# 16V3_EDA.net
KiCad netlist of a schematic drawn in EasyEDA Pro
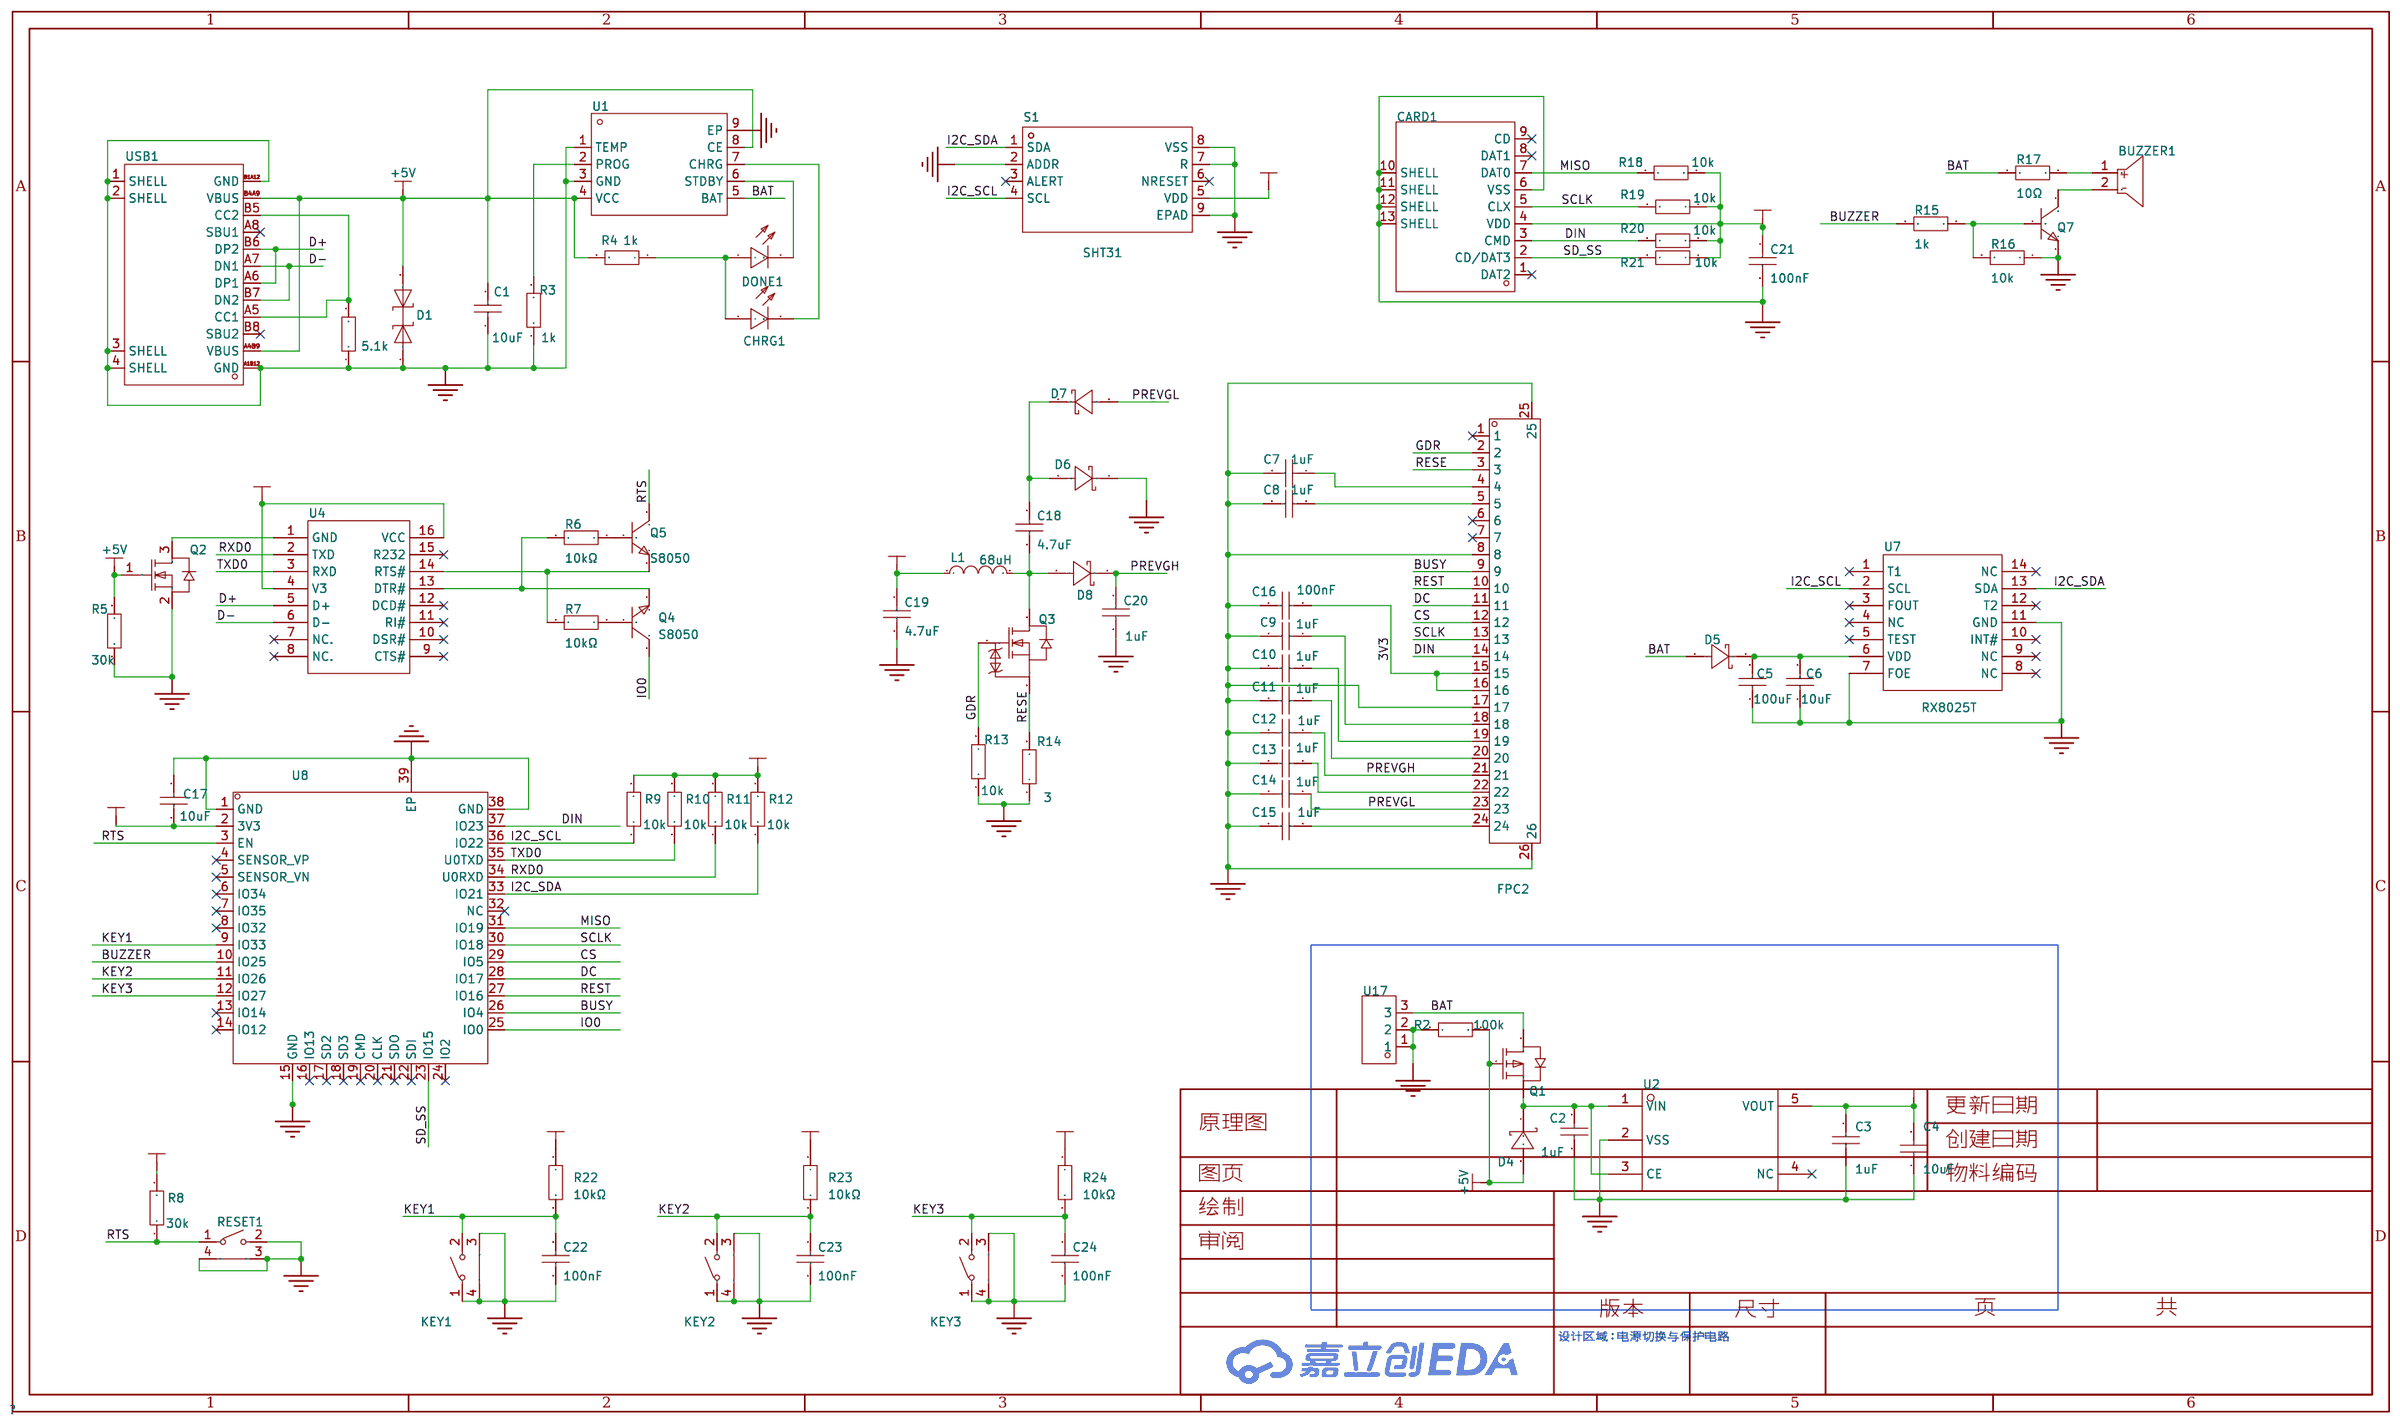
[diagram p0: schematic sheet]

(export (version "E")
  (design (tool "Eeschema 10.0.6"))
  (components
    (comp (ref "BUZZER1")
      (value "FMQ-BUZZER2")
      (footprint "easyedapro:BUZ-TH_BD12.0-P7.60-D0.6-FD")
      (libsource (lib "easyedapro") (part "FMQ-BUZZER2"))
    )
    (comp (ref "C1")
      (value "10uF")
      (footprint "easyedapro:C0805")
      (fields
        (field (name "Manufacturer Part") "CC0805KRX7R9BB104")
        (field (name "Manufacturer") "YAGEO(国巨)")
      )
      (libsource (lib "easyedapro") (part "CC0805KRX7R9BB104"))
    )
    (comp (ref "C2")
      (value "1uF")
      (footprint "easyedapro:C0805")
      (fields
        (field (name "Manufacturer Part") "CC0805KRX7R9BB104")
        (field (name "Manufacturer") "YAGEO(国巨)")
      )
      (libsource (lib "easyedapro") (part "CC0805KRX7R9BB104"))
    )
    (comp (ref "C3")
      (value "1uF")
      (footprint "easyedapro:C0805")
      (fields
        (field (name "Manufacturer Part") "CC0805KRX7R9BB104")
        (field (name "Manufacturer") "YAGEO(国巨)")
      )
      (libsource (lib "easyedapro") (part "CC0805KRX7R9BB104"))
    )
    (comp (ref "C4")
      (value "10uF")
      (footprint "easyedapro:C0805")
      (fields
        (field (name "Manufacturer Part") "CC0805KRX7R9BB104")
        (field (name "Manufacturer") "YAGEO(国巨)")
      )
      (libsource (lib "easyedapro") (part "CC0805KRX7R9BB104"))
    )
    (comp (ref "C5")
      (value "100uF")
      (footprint "easyedapro:C0805")
      (description "容值:100nF;精度:±10%;额定电压:50V;温度系数:X7R;")
      (fields
        (field (name "Manufacturer Part") "CC0805KRX7R9BB104")
        (field (name "Manufacturer") "YAGEO(国巨)")
      )
      (libsource (lib "easyedapro") (part "CC0805KRX7R9BB104"))
    )
    (comp (ref "C6")
      (value "10uF")
      (footprint "easyedapro:C0805")
      (fields
        (field (name "Manufacturer Part") "CC0805KRX7R9BB104")
        (field (name "Manufacturer") "YAGEO(国巨)")
      )
      (libsource (lib "easyedapro") (part "CC0805KRX7R9BB104"))
    )
    (comp (ref "C7")
      (value "1uF")
      (footprint "easyedapro:C0805")
      (fields
        (field (name "Manufacturer Part") "CC0805KRX7R9BB104")
        (field (name "Manufacturer") "YAGEO(国巨)")
      )
      (libsource (lib "easyedapro") (part "CC0805KRX7R9BB104"))
    )
    (comp (ref "C8")
      (value "1uF")
      (footprint "easyedapro:C0805")
      (fields
        (field (name "Manufacturer Part") "CC0805KRX7R9BB104")
        (field (name "Manufacturer") "YAGEO(国巨)")
      )
      (libsource (lib "easyedapro") (part "CC0805KRX7R9BB104"))
    )
    (comp (ref "C9")
      (value "1uF")
      (footprint "easyedapro:C0805")
      (fields
        (field (name "Manufacturer Part") "CC0805KRX7R9BB104")
        (field (name "Manufacturer") "YAGEO(国巨)")
      )
      (libsource (lib "easyedapro") (part "CC0805KRX7R9BB104"))
    )
    (comp (ref "C10")
      (value "1uF")
      (footprint "easyedapro:C0805")
      (fields
        (field (name "Manufacturer Part") "CC0805KRX7R9BB104")
        (field (name "Manufacturer") "YAGEO(国巨)")
      )
      (libsource (lib "easyedapro") (part "CC0805KRX7R9BB104"))
    )
    (comp (ref "C11")
      (value "1uF")
      (footprint "easyedapro:C0805")
      (fields
        (field (name "Manufacturer Part") "CC0805KRX7R9BB104")
        (field (name "Manufacturer") "YAGEO(国巨)")
      )
      (libsource (lib "easyedapro") (part "CC0805KRX7R9BB104"))
    )
    (comp (ref "C12")
      (value "1uF")
      (footprint "easyedapro:C0805")
      (fields
        (field (name "Manufacturer Part") "CC0805KRX7R9BB104")
        (field (name "Manufacturer") "YAGEO(国巨)")
      )
      (libsource (lib "easyedapro") (part "CC0805KRX7R9BB104"))
    )
    (comp (ref "C13")
      (value "1uF")
      (footprint "easyedapro:C0805")
      (fields
        (field (name "Manufacturer Part") "CC0805KRX7R9BB104")
        (field (name "Manufacturer") "YAGEO(国巨)")
      )
      (libsource (lib "easyedapro") (part "CC0805KRX7R9BB104"))
    )
    (comp (ref "C14")
      (value "1uF")
      (footprint "easyedapro:C0805")
      (fields
        (field (name "Manufacturer Part") "CC0805KRX7R9BB104")
        (field (name "Manufacturer") "YAGEO(国巨)")
      )
      (libsource (lib "easyedapro") (part "CC0805KRX7R9BB104"))
    )
    (comp (ref "C15")
      (value "1uF")
      (footprint "easyedapro:C0805")
      (fields
        (field (name "Manufacturer Part") "CC0805KRX7R9BB104")
        (field (name "Manufacturer") "YAGEO(国巨)")
      )
      (libsource (lib "easyedapro") (part "CC0805KRX7R9BB104"))
    )
    (comp (ref "C16")
      (value "100nF")
      (footprint "easyedapro:C0805")
      (description "容值:100nF;精度:±10%;额定电压:50V;温度系数:X7R;")
      (fields
        (field (name "Manufacturer Part") "CC0805KRX7R9BB104")
        (field (name "Manufacturer") "YAGEO(国巨)")
      )
      (libsource (lib "easyedapro") (part "CC0805KRX7R9BB104"))
    )
    (comp (ref "C17")
      (value "10uF")
      (footprint "easyedapro:C0805")
      (fields
        (field (name "Manufacturer Part") "CC0805KRX7R9BB104")
        (field (name "Manufacturer") "YAGEO(国巨)")
      )
      (libsource (lib "easyedapro") (part "CC0805KRX7R9BB104"))
    )
    (comp (ref "C18")
      (value "4.7uF")
      (footprint "easyedapro:C0805")
      (description "容值:100nF;精度:±10%;额定电压:50V;温度系数:X7R;")
      (fields
        (field (name "Manufacturer Part") "CC0805KRX7R9BB104")
        (field (name "Manufacturer") "YAGEO(国巨)")
      )
      (libsource (lib "easyedapro") (part "CC0805KRX7R9BB104"))
    )
    (comp (ref "C19")
      (value "4.7uF")
      (footprint "easyedapro:C0805")
      (fields
        (field (name "Manufacturer Part") "CC0805KRX7R9BB104")
        (field (name "Manufacturer") "YAGEO(国巨)")
      )
      (libsource (lib "easyedapro") (part "CC0805KRX7R9BB104"))
    )
    (comp (ref "C20")
      (value "1uF")
      (footprint "easyedapro:C0805")
      (fields
        (field (name "Manufacturer Part") "CC0805KRX7R9BB104")
        (field (name "Manufacturer") "YAGEO(国巨)")
      )
      (libsource (lib "easyedapro") (part "CC0805KRX7R9BB104"))
    )
    (comp (ref "C21")
      (value "100nF")
      (footprint "easyedapro:C0805")
      (description "容值:100nF;精度:±10%;额定电压:50V;温度系数:X7R;")
      (fields
        (field (name "Manufacturer Part") "CC0805KRX7R9BB104")
        (field (name "Manufacturer") "YAGEO(国巨)")
      )
      (libsource (lib "easyedapro") (part "CC0805KRX7R9BB104"))
    )
    (comp (ref "C22")
      (value "100nF")
      (footprint "easyedapro:C0805")
      (fields
        (field (name "Manufacturer Part") "CC0805KRX7R9BB104")
        (field (name "Manufacturer") "YAGEO(国巨)")
      )
      (libsource (lib "easyedapro") (part "CC0805KRX7R9BB104"))
    )
    (comp (ref "C23")
      (value "100nF")
      (footprint "easyedapro:C0805")
      (fields
        (field (name "Manufacturer Part") "CC0805KRX7R9BB104")
        (field (name "Manufacturer") "YAGEO(国巨)")
      )
      (libsource (lib "easyedapro") (part "CC0805KRX7R9BB104"))
    )
    (comp (ref "C24")
      (value "100nF")
      (footprint "easyedapro:C0805")
      (fields
        (field (name "Manufacturer Part") "CC0805KRX7R9BB104")
        (field (name "Manufacturer") "YAGEO(国巨)")
      )
      (libsource (lib "easyedapro") (part "CC0805KRX7R9BB104"))
    )
    (comp (ref "CARD1")
      (value "~")
      (footprint "easyedapro:TF-SMD_THD2528-11SD-GF")
      (description "卡连接方式:自弹式;卡类型:MicroSD卡(TF卡);连接器类型:卡座;本体最大高度:2mm;工作温度范围:-;")
      (fields (field (name "Manufacturer Part") "THD2528-11SD-GF") (field (name "Manufacturer") "THD(台华达)"))
      (libsource (lib "easyedapro") (part "THD2528-11SD-GF"))
    )
    (comp (ref "CHRG1")
      (value "~")
      (footprint "easyedapro:LED0603-R-RD")
      (fields
        (field (name "Manufacturer Part") "19-217/R6C-AL1M2VY/3T")
        (field (name "Manufacturer") "EVERLIGHT(台湾亿光)")
      )
      (libsource (lib "easyedapro") (part "19-217/R6C-AL1M2VY/3T"))
    )
    (comp (ref "D1")
      (value "~")
      (footprint "easyedapro:SOD-523_L1.2-W0.8-LS1.6-BI")
      (description "极性:双向;反向截止电压(Vrwm):5V@(最大值);击穿电压(最小值):5.6V;峰值脉冲电流(Ipp)@10/1000s:4A;最大钳位电压:12V;")
      (fields (field (name "Manufacturer Part") "ESD5Z5.0VC") (field (name "Manufacturer") "TC(德昌)"))
      (libsource (lib "easyedapro") (part "ESD5Z5.0VC"))
    )
    (comp (ref "D4")
      (value "~")
      (footprint "easyedapro:SMA_L4.3-W2.6-LS5.1-RD")
      (description "直流反向耐压(Vr):40V;平均整流电流(Io):3A;正向压降(Vf):550mV@3A;")
      (fields (field (name "Manufacturer Part") "SS34") (field (name "Manufacturer") "SINO-IC(光宇睿芯)"))
      (libsource (lib "easyedapro") (part "SS34_C355267"))
    )
    (comp (ref "D5")
      (value "~")
      (footprint "easyedapro:SOD-123_L2.7-W1.6-LS3.7-RD-1")
      (description "直流反向耐压(Vr):30V;平均整流电流(Io):500mA;正向压降(Vf):550mV@500mA;")
      (fields (field (name "Manufacturer Part") "MBR0530") (field (name "Manufacturer") "YANGJIE(扬杰)"))
      (libsource (lib "easyedapro") (part "MBR0530_C699108"))
    )
    (comp (ref "D6")
      (value "~")
      (footprint "easyedapro:SOD-123_L2.7-W1.6-LS3.7-RD-1")
      (description "直流反向耐压(Vr):30V;平均整流电流(Io):500mA;正向压降(Vf):550mV@500mA;")
      (fields (field (name "Manufacturer Part") "MBR0530") (field (name "Manufacturer") "YANGJIE(扬杰)"))
      (libsource (lib "easyedapro") (part "MBR0530_C699108"))
    )
    (comp (ref "D7")
      (value "~")
      (footprint "easyedapro:SOD-123_L2.7-W1.6-LS3.7-RD-1")
      (description "直流反向耐压(Vr):30V;平均整流电流(Io):500mA;正向压降(Vf):550mV@500mA;")
      (fields (field (name "Manufacturer Part") "MBR0530") (field (name "Manufacturer") "YANGJIE(扬杰)"))
      (libsource (lib "easyedapro") (part "MBR0530_C699108"))
    )
    (comp (ref "D8")
      (value "~")
      (footprint "easyedapro:SOD-123_L2.7-W1.6-LS3.7-RD-1")
      (description "直流反向耐压(Vr):30V;平均整流电流(Io):500mA;正向压降(Vf):550mV@500mA;")
      (fields (field (name "Manufacturer Part") "MBR0530") (field (name "Manufacturer") "YANGJIE(扬杰)"))
      (libsource (lib "easyedapro") (part "MBR0530_C699108"))
    )
    (comp (ref "DONE1")
      (value "~")
      (footprint "easyedapro:LED0603-R-RD")
      (fields
        (field (name "Manufacturer Part") "19-217/R6C-AL1M2VY/3T")
        (field (name "Manufacturer") "EVERLIGHT(台湾亿光)")
      )
      (libsource (lib "easyedapro") (part "19-217/R6C-AL1M2VY/3T"))
    )
    (comp (ref "FPC2")
      (value "~")
      (footprint "easyedapro:FPC-SMD_24P-L17.5-W5.4-P0.50")
      (description "间距:0.5mm;触点数量:24;锁定特性:抽屉式;安装类型:卧贴;触点类型:上接;")
      (fields (field (name "Manufacturer Part") "AFC07-S24ECC-00") (field (name "Manufacturer") "JS(钜硕电子)"))
      (libsource (lib "easyedapro") (part "FPC 0.5MM 24P Pull type H2.0mm Pick up"))
    )
    (comp (ref "KEY1")
      (value "~")
      (footprint "easyedapro:SW-SMD_L4.7-W3.5-P3.35-EH")
      (fields
        (field (name "Manufacturer Part") "GT-TC018B-H0375-L1")
        (field (name "Manufacturer") "G-Switch(品赞)")
      )
      (libsource (lib "easyedapro") (part "GT-TC018B-H0375-L1"))
    )
    (comp (ref "KEY2")
      (value "~")
      (footprint "easyedapro:SW-SMD_L4.7-W3.5-P3.35-EH")
      (fields
        (field (name "Manufacturer Part") "GT-TC018B-H0375-L1")
        (field (name "Manufacturer") "G-Switch(品赞)")
      )
      (libsource (lib "easyedapro") (part "GT-TC018B-H0375-L1"))
    )
    (comp (ref "KEY3")
      (value "~")
      (footprint "easyedapro:SW-SMD_L4.7-W3.5-P3.35-EH")
      (fields
        (field (name "Manufacturer Part") "GT-TC018B-H0375-L1")
        (field (name "Manufacturer") "G-Switch(品赞)")
      )
      (libsource (lib "easyedapro") (part "GT-TC018B-H0375-L1"))
    )
    (comp (ref "L1")
      (value "68uH")
      (footprint "easyedapro:IND-SMD_L4.0-W4.0")
      (description "电感值:68uH;精度:±20%;额定电流:-;直流电阻(DCR):-;")
      (fields (field (name "Manufacturer Part") "CR4020-680M") (field (name "Manufacturer") "ceaiya(柯爱亚)"))
      (libsource (lib "easyedapro") (part "CR4020-680M"))
    )
    (comp (ref "Q1")
      (value "~")
      (footprint "easyedapro:SOT-23_L2.9-W1.3-P1.90-LS2.4-BR")
      (fields (field (name "Manufacturer Part") "SI2305") (field (name "Manufacturer") "BORN伯恩半导体"))
      (libsource (lib "easyedapro") (part "SI2305_C344006"))
    )
    (comp (ref "Q2")
      (value "~")
      (footprint "easyedapro:SOT-23_L2.9-W1.3-P1.90-LS2.4-BR")
      (fields (field (name "Manufacturer Part") "AO3402") (field (name "Manufacturer") "GOODWORK(固得沃克)"))
      (libsource (lib "easyedapro") (part "AO3402_C2938369"))
    )
    (comp (ref "Q3")
      (value "~")
      (footprint "easyedapro:SOT-323_L2.0-W1.3-P1.30-LS2.1-BR")
      (fields
        (field (name "Manufacturer Part") "SI1308EDL-T1-GE3")
        (field (name "Manufacturer") "VISHAY(威世)")
      )
      (libsource (lib "easyedapro") (part "SI1308EDL-T1-GE3"))
    )
    (comp (ref "Q4")
      (value "S8050")
      (footprint "easyedapro:SOT-23-3_L3.0-W1.7-P0.95-LS2.9-BR")
      (fields (field (name "Manufacturer") "CJ"))
      (libsource (lib "easyedapro") (part "S8050"))
    )
    (comp (ref "Q5")
      (value "S8050")
      (footprint "easyedapro:SOT-23-3_L3.0-W1.7-P0.95-LS2.9-BR(1)")
      (fields (field (name "Manufacturer") "CJ"))
      (libsource (lib "") (part "S8050_1"))
    )
    (comp (ref "Q7")
      (value "S8050-J3Y")
      (footprint "easyedapro:SOT-23-3_L3.0-W1.7-P0.95-LS2.9-BR")
      (fields (field (name "Manufacturer") "(MDD) Jiangsu Yutai Elec"))
      (libsource (lib "easyedapro") (part "S8050-J3Y"))
    )
    (comp (ref "R1")
      (value "5.1k")
      (footprint "easyedapro:R0603")
      (description "电阻类型:薄膜电阻;阻值:10k;精度:±0.1%;功率:100mW;温度系数:±25ppm/;最大工作电压:75V;工作温度范围:-55~+155;")
      (fields
        (field (name "Manufacturer Part") "TR0603B10K0P0525Z")
        (field (name "Manufacturer") "EVER OHMS(天二科技)")
      )
      (libsource (lib "easyedapro") (part "TR0603B10KP05250.1W"))
    )
    (comp (ref "R2")
      (value "100k")
      (footprint "easyedapro:R0603")
      (description "电阻类型:薄膜电阻;阻值:10k;精度:±0.1%;功率:100mW;温度系数:±25ppm/;最大工作电压:75V;工作温度范围:-55~+155;")
      (fields
        (field (name "Manufacturer Part") "TR0603B10K0P0525Z")
        (field (name "Manufacturer") "EVER OHMS(天二科技)")
      )
      (libsource (lib "easyedapro") (part "TR0603B10KP05250.1W"))
    )
    (comp (ref "R3")
      (value "1k")
      (footprint "easyedapro:R0603")
      (description "电阻类型:薄膜电阻;阻值:10k;精度:±0.1%;功率:100mW;温度系数:±25ppm/;最大工作电压:75V;工作温度范围:-55~+155;")
      (fields
        (field (name "Manufacturer Part") "TR0603B10K0P0525Z")
        (field (name "Manufacturer") "EVER OHMS(天二科技)")
      )
      (libsource (lib "easyedapro") (part "TR0603B10KP05250.1W"))
    )
    (comp (ref "R4")
      (value "1k")
      (footprint "easyedapro:R0603")
      (description "电阻类型:薄膜电阻;阻值:10k;精度:±0.1%;功率:100mW;温度系数:±25ppm/;最大工作电压:75V;工作温度范围:-55~+155;")
      (fields
        (field (name "Manufacturer Part") "TR0603B10K0P0525Z")
        (field (name "Manufacturer") "EVER OHMS(天二科技)")
      )
      (libsource (lib "easyedapro") (part "TR0603B10KP05250.1W"))
    )
    (comp (ref "R5")
      (value "30k")
      (footprint "easyedapro:R0603")
      (description "电阻类型:薄膜电阻;阻值:10k;精度:±0.1%;功率:100mW;温度系数:±25ppm/;最大工作电压:75V;工作温度范围:-55~+155;")
      (fields
        (field (name "Manufacturer Part") "TR0603B10K0P0525Z")
        (field (name "Manufacturer") "EVER OHMS(天二科技)")
      )
      (libsource (lib "easyedapro") (part "TR0603B10KP05250.1W"))
    )
    (comp (ref "R6")
      (value "10kΩ")
      (footprint "easyedapro:R0603")
      (description "电阻类型:薄膜电阻;阻值:10k;精度:±0.1%;功率:100mW;温度系数:±25ppm/;最大工作电压:75V;工作温度范围:-55~+155;")
      (fields
        (field (name "Manufacturer Part") "TR0603B10K0P0525Z")
        (field (name "Manufacturer") "EVER OHMS(天二科技)")
      )
      (libsource (lib "easyedapro") (part "TR0603B10KP05250.1W"))
    )
    (comp (ref "R7")
      (value "10kΩ")
      (footprint "easyedapro:R0603")
      (description "电阻类型:薄膜电阻;阻值:10k;精度:±0.1%;功率:100mW;温度系数:±25ppm/;最大工作电压:75V;工作温度范围:-55~+155;")
      (fields
        (field (name "Manufacturer Part") "TR0603B10K0P0525Z")
        (field (name "Manufacturer") "EVER OHMS(天二科技)")
      )
      (libsource (lib "easyedapro") (part "TR0603B10KP05250.1W"))
    )
    (comp (ref "R8")
      (value "30k")
      (footprint "easyedapro:R0603")
      (description "电阻类型:薄膜电阻;阻值:10k;精度:±0.1%;功率:100mW;温度系数:±25ppm/;最大工作电压:75V;工作温度范围:-55~+155;")
      (fields
        (field (name "Manufacturer Part") "TR0603B10K0P0525Z")
        (field (name "Manufacturer") "EVER OHMS(天二科技)")
      )
      (libsource (lib "easyedapro") (part "TR0603B10KP05250.1W"))
    )
    (comp (ref "R9")
      (value "10k")
      (footprint "easyedapro:R0603")
      (description "电阻类型:薄膜电阻;阻值:10k;精度:±0.1%;功率:100mW;温度系数:±25ppm/;最大工作电压:75V;工作温度范围:-55~+155;")
      (fields
        (field (name "Manufacturer Part") "TR0603B10K0P0525Z")
        (field (name "Manufacturer") "EVER OHMS(天二科技)")
      )
      (libsource (lib "easyedapro") (part "TR0603B10KP05250.1W"))
    )
    (comp (ref "R10")
      (value "10k")
      (footprint "easyedapro:R0603")
      (description "电阻类型:薄膜电阻;阻值:10k;精度:±0.1%;功率:100mW;温度系数:±25ppm/;最大工作电压:75V;工作温度范围:-55~+155;")
      (fields
        (field (name "Manufacturer Part") "TR0603B10K0P0525Z")
        (field (name "Manufacturer") "EVER OHMS(天二科技)")
      )
      (libsource (lib "easyedapro") (part "TR0603B10KP05250.1W"))
    )
    (comp (ref "R11")
      (value "10k")
      (footprint "easyedapro:R0603")
      (description "电阻类型:薄膜电阻;阻值:10k;精度:±0.1%;功率:100mW;温度系数:±25ppm/;最大工作电压:75V;工作温度范围:-55~+155;")
      (fields
        (field (name "Manufacturer Part") "TR0603B10K0P0525Z")
        (field (name "Manufacturer") "EVER OHMS(天二科技)")
      )
      (libsource (lib "easyedapro") (part "TR0603B10KP05250.1W"))
    )
    (comp (ref "R12")
      (value "10k")
      (footprint "easyedapro:R0603")
      (description "电阻类型:薄膜电阻;阻值:10k;精度:±0.1%;功率:100mW;温度系数:±25ppm/;最大工作电压:75V;工作温度范围:-55~+155;")
      (fields
        (field (name "Manufacturer Part") "TR0603B10K0P0525Z")
        (field (name "Manufacturer") "EVER OHMS(天二科技)")
      )
      (libsource (lib "easyedapro") (part "TR0603B10KP05250.1W"))
    )
    (comp (ref "R13")
      (value "10k")
      (footprint "easyedapro:R0603")
      (description "电阻类型:薄膜电阻;阻值:10k;精度:±0.1%;功率:100mW;温度系数:±25ppm/;最大工作电压:75V;工作温度范围:-55~+155;")
      (fields
        (field (name "Manufacturer Part") "TR0603B10K0P0525Z")
        (field (name "Manufacturer") "EVER OHMS(天二科技)")
      )
      (libsource (lib "easyedapro") (part "TR0603B10KP05250.1W"))
    )
    (comp (ref "R14")
      (value "3")
      (footprint "easyedapro:R0603")
      (description "电阻类型:薄膜电阻;阻值:10k;精度:±0.1%;功率:100mW;温度系数:±25ppm/;最大工作电压:75V;工作温度范围:-55~+155;")
      (fields
        (field (name "Manufacturer Part") "TR0603B10K0P0525Z")
        (field (name "Manufacturer") "EVER OHMS(天二科技)")
      )
      (libsource (lib "easyedapro") (part "TR0603B10KP05250.1W"))
    )
    (comp (ref "R15")
      (value "1k")
      (footprint "easyedapro:R0603")
      (description "电阻类型:薄膜电阻;阻值:10k;精度:±0.1%;功率:100mW;温度系数:±25ppm/;最大工作电压:75V;工作温度范围:-55~+155;")
      (fields
        (field (name "Manufacturer Part") "TR0603B10K0P0525Z")
        (field (name "Manufacturer") "EVER OHMS(天二科技)")
      )
      (libsource (lib "easyedapro") (part "TR0603B10KP05250.1W"))
    )
    (comp (ref "R16")
      (value "10k")
      (footprint "easyedapro:R0603")
      (description "电阻类型:薄膜电阻;阻值:10k;精度:±0.1%;功率:100mW;温度系数:±25ppm/;最大工作电压:75V;工作温度范围:-55~+155;")
      (fields
        (field (name "Manufacturer Part") "TR0603B10K0P0525Z")
        (field (name "Manufacturer") "EVER OHMS(天二科技)")
      )
      (libsource (lib "easyedapro") (part "TR0603B10KP05250.1W"))
    )
    (comp (ref "R17")
      (value "10Ω")
      (footprint "easyedapro:R0603")
      (description "电阻类型:厚膜电阻;阻值:10Ω;精度:±1%;功率:100mW;")
      (fields
        (field (name "Manufacturer Part") "0603WAF100JT5E")
        (field (name "Manufacturer") "UNI-ROYAL(厚声)")
      )
      (libsource (lib "easyedapro") (part "0603WAF100JT5E"))
    )
    (comp (ref "R18")
      (value "10k")
      (footprint "easyedapro:R0603")
      (description "电阻类型:薄膜电阻;阻值:10k;精度:±0.1%;功率:100mW;温度系数:±25ppm/;最大工作电压:75V;工作温度范围:-55~+155;")
      (fields
        (field (name "Manufacturer Part") "TR0603B10K0P0525Z")
        (field (name "Manufacturer") "EVER OHMS(天二科技)")
      )
      (libsource (lib "easyedapro") (part "TR0603B10KP05250.1W"))
    )
    (comp (ref "R19")
      (value "10k")
      (footprint "easyedapro:R0603")
      (description "电阻类型:薄膜电阻;阻值:10k;精度:±0.1%;功率:100mW;温度系数:±25ppm/;最大工作电压:75V;工作温度范围:-55~+155;")
      (fields
        (field (name "Manufacturer Part") "TR0603B10K0P0525Z")
        (field (name "Manufacturer") "EVER OHMS(天二科技)")
      )
      (libsource (lib "easyedapro") (part "TR0603B10KP05250.1W"))
    )
    (comp (ref "R20")
      (value "10k")
      (footprint "easyedapro:R0603")
      (description "电阻类型:薄膜电阻;阻值:10k;精度:±0.1%;功率:100mW;温度系数:±25ppm/;最大工作电压:75V;工作温度范围:-55~+155;")
      (fields
        (field (name "Manufacturer Part") "TR0603B10K0P0525Z")
        (field (name "Manufacturer") "EVER OHMS(天二科技)")
      )
      (libsource (lib "easyedapro") (part "TR0603B10KP05250.1W"))
    )
    (comp (ref "R21")
      (value "10k")
      (footprint "easyedapro:R0603")
      (description "电阻类型:薄膜电阻;阻值:10k;精度:±0.1%;功率:100mW;温度系数:±25ppm/;最大工作电压:75V;工作温度范围:-55~+155;")
      (fields
        (field (name "Manufacturer Part") "TR0603B10K0P0525Z")
        (field (name "Manufacturer") "EVER OHMS(天二科技)")
      )
      (libsource (lib "easyedapro") (part "TR0603B10KP05250.1W"))
    )
    (comp (ref "R22")
      (value "10kΩ")
      (footprint "easyedapro:R0603")
      (description "电阻类型:薄膜电阻;阻值:10k;精度:±0.1%;功率:100mW;温度系数:±25ppm/;最大工作电压:75V;工作温度范围:-55~+155;")
      (fields
        (field (name "Manufacturer Part") "TR0603B10K0P0525Z")
        (field (name "Manufacturer") "EVER OHMS(天二科技)")
      )
      (libsource (lib "easyedapro") (part "TR0603B10KP05250.1W"))
    )
    (comp (ref "R23")
      (value "10kΩ")
      (footprint "easyedapro:R0603")
      (description "电阻类型:薄膜电阻;阻值:10k;精度:±0.1%;功率:100mW;温度系数:±25ppm/;最大工作电压:75V;工作温度范围:-55~+155;")
      (fields
        (field (name "Manufacturer Part") "TR0603B10K0P0525Z")
        (field (name "Manufacturer") "EVER OHMS(天二科技)")
      )
      (libsource (lib "easyedapro") (part "TR0603B10KP05250.1W"))
    )
    (comp (ref "R24")
      (value "10kΩ")
      (footprint "easyedapro:R0603")
      (description "电阻类型:薄膜电阻;阻值:10k;精度:±0.1%;功率:100mW;温度系数:±25ppm/;最大工作电压:75V;工作温度范围:-55~+155;")
      (fields
        (field (name "Manufacturer Part") "TR0603B10K0P0525Z")
        (field (name "Manufacturer") "EVER OHMS(天二科技)")
      )
      (libsource (lib "easyedapro") (part "TR0603B10KP05250.1W"))
    )
    (comp (ref "RESET1")
      (value "~")
      (footprint "easyedapro:SW-SMD_L4.7-W3.5-P3.35-EH")
      (fields
        (field (name "Manufacturer Part") "GT-TC018B-H0375-L1")
        (field (name "Manufacturer") "G-Switch(品赞)")
      )
      (libsource (lib "easyedapro") (part "GT-TC018B-H0375-L1"))
    )
    (comp (ref "S1")
      (value "SHT31")
      (footprint "easyedapro:DFN-8_L2.5-W2.5-P0.50-BL-EP")
      (description "1-101386-01")
      (fields (field (name "Manufacturer") "Sensirion(瑞士盛思锐)"))
      (libsource (lib "easyedapro") (part "SHT31-DIS-B"))
    )
    (comp (ref "U1")
      (value "~")
      (footprint "easyedapro:ESOP-8_L4.9-W3.9-P1.27-LS6.0-BL-EP")
      (description "充电电池的类型:-;电池单元组数:-;最大充电电流:-;充满的电池组电压:-;最大供应电压:-;")
      (fields (field (name "Manufacturer Part") "TP4056") (field (name "Manufacturer") "UMW(友台半导体)"))
      (libsource (lib "easyedapro") (part "TP4056_C725790"))
    )
    (comp (ref "U2") (value "~") (libsource (lib "easyedapro") (part "LDO")))
    (comp (ref "U4")
      (value "~")
      (footprint "easyedapro:SOP-16_L10.0-W3.9-P1.27-LS6.0-BL")
      (description "类型:Transceiver;协议类别:USB 2.0;驱动器/接收器数:-;数据速率:2Mbps;")
      (fields (field (name "Manufacturer Part") "CH340C") (field (name "Manufacturer") "WCH(南京沁恒)"))
      (libsource (lib "easyedapro") (part "CH340C"))
    )
    (comp (ref "U7")
      (value "RX8025T")
      (footprint "easyedapro:SOIC-14_L10.0-W5.5-P1.27-LS7.8-BL")
      (description "时钟芯片类型:Clock/Calendar;存储器容量:-;时间格式:HH:MM:SS;日期格式:YY-MM-DD;接口类型:I2C;")
      (fields (field (name "Manufacturer Part") "RX8025T-UB") (field (name "Manufacturer") "EPSON(爱普生)"))
      (libsource (lib "easyedapro") (part "RX8025T-UB"))
    )
    (comp (ref "U8")
      (value "~")
      (footprint "easyedapro:WIRELM-SMD_ESP32-S")
      (fields (field (name "Manufacturer Part") "ESP32-S") (field (name "Manufacturer") "Ai-Thinker(安信可)"))
      (libsource (lib "easyedapro") (part "ESP32-S"))
    )
    (comp (ref "U17")
      (value "ZX-XH2.54-3PZZ")
      (footprint "easyedapro:CONN-TH_3P-P2.54_2501S-3P")
      (fields (field (name "Manufacturer") "Megastar(兆星)"))
      (libsource (lib "easyedapro") (part "ZX-XH2.54-3PZZ"))
    )
    (comp (ref "USB1")
      (value "~")
      (footprint "easyedapro:USB-SMD_TYPE-611S-T3")
      (description "连接器类型:Type-C;标准:-;公母:母座;触点数量:16;端口数量:1;安装方式:卧贴;额定电流 - 电源:3A;工作温度范围:-25~+85;")
      (fields (field (name "Manufacturer Part") "TYPE-611S-T3") (field (name "Manufacturer") "Yuandi(台湾元迪)"))
      (libsource (lib "easyedapro") (part "TYPE-611S-T3"))
    )
  )
  (nets
    (net (code "1") (name "+5V") (class "Default")
      (node (ref "C1") (pin "2") (pinfunction "2_2") (pintype "input"))
      (node (ref "D1") (pin "2") (pinfunction "2_2") (pintype "input"))
      (node (ref "D4") (pin "2") (pinfunction "A_2") (pintype "input"))
      (node (ref "Q1") (pin "1") (pinfunction "G_1") (pintype "input"))
      (node (ref "Q2") (pin "1") (pinfunction "G_1") (pintype "input"))
      (node (ref "R2") (pin "2") (pinfunction "2_2") (pintype "input"))
      (node (ref "R4") (pin "2") (pinfunction "2_2") (pintype "input"))
      (node (ref "R5") (pin "2") (pinfunction "2_2") (pintype "input"))
      (node (ref "U1") (pin "4") (pinfunction "VCC_4") (pintype "input"))
      (node (ref "U1") (pin "8") (pinfunction "CE_8") (pintype "input"))
      (node (ref "USB1") (pin "A4B9") (pinfunction "VBUS_A4B9") (pintype "input"))
      (node (ref "USB1") (pin "B4A9") (pinfunction "VBUS_B4A9") (pintype "input"))
    )
    (net (code "2") (name "/BAT") (class "Default")
      (node (ref "D5") (pin "2") (pinfunction "A_2") (pintype "input"))
      (node (ref "Q1") (pin "3") (pinfunction "D_3") (pintype "input"))
      (node (ref "R17") (pin "1") (pinfunction "1_1") (pintype "input"))
      (node (ref "U1") (pin "5") (pinfunction "BAT_5") (pintype "input"))
      (node (ref "U17") (pin "3") (pinfunction "3_3") (pintype "unspecified"))
    )
    (net (code "3") (name "/BUSY") (class "Default")
      (node (ref "FPC2") (pin "9") (pinfunction "9_9") (pintype "input"))
      (node (ref "U8") (pin "26") (pinfunction "IO4_26") (pintype "input"))
    )
    (net (code "4") (name "/BUZZER") (class "Default")
      (node (ref "R15") (pin "2") (pinfunction "2_2") (pintype "input"))
      (node (ref "U8") (pin "10") (pinfunction "IO25_10") (pintype "input"))
    )
    (net (code "5") (name "/CS") (class "Default")
      (node (ref "FPC2") (pin "12") (pinfunction "12_12") (pintype "input"))
      (node (ref "U8") (pin "29") (pinfunction "IO5_29") (pintype "input"))
    )
    (net (code "6") (name "/D+") (class "Default")
      (node (ref "U4") (pin "5") (pinfunction "D+_5") (pintype "input"))
      (node (ref "USB1") (pin "A6") (pinfunction "DP1_A6") (pintype "input"))
      (node (ref "USB1") (pin "B6") (pinfunction "DP2_B6") (pintype "input"))
    )
    (net (code "7") (name "/D-") (class "Default")
      (node (ref "U4") (pin "6") (pinfunction "D-_6") (pintype "input"))
      (node (ref "USB1") (pin "A7") (pinfunction "DN1_A7") (pintype "input"))
      (node (ref "USB1") (pin "B7") (pinfunction "DN2_B7") (pintype "input"))
    )
    (net (code "8") (name "/DC") (class "Default")
      (node (ref "FPC2") (pin "11") (pinfunction "11_11") (pintype "input"))
      (node (ref "U8") (pin "28") (pinfunction "IO17_28") (pintype "input"))
    )
    (net (code "9") (name "/DIN") (class "Default")
      (node (ref "CARD1") (pin "3") (pinfunction "CMD_3") (pintype "input"))
      (node (ref "FPC2") (pin "14") (pinfunction "14_14") (pintype "input"))
      (node (ref "R20") (pin "2") (pinfunction "2_2") (pintype "input"))
      (node (ref "U8") (pin "37") (pinfunction "IO23_37") (pintype "input"))
    )
    (net (code "10") (name "/GDR") (class "Default")
      (node (ref "FPC2") (pin "2") (pinfunction "2_2") (pintype "input"))
      (node (ref "Q3") (pin "1") (pinfunction "G_1") (pintype "input"))
      (node (ref "R13") (pin "2") (pinfunction "2_2") (pintype "input"))
    )
    (net (code "11") (name "/I2C_SCL") (class "Default")
      (node (ref "R9") (pin "1") (pinfunction "1_1") (pintype "input"))
      (node (ref "S1") (pin "4") (pinfunction "SCL_4") (pintype "unspecified"))
      (node (ref "U7") (pin "2") (pinfunction "SCL_2") (pintype "input"))
      (node (ref "U8") (pin "36") (pinfunction "IO22_36") (pintype "input"))
    )
    (net (code "12") (name "/I2C_SDA") (class "Default")
      (node (ref "R12") (pin "1") (pinfunction "1_1") (pintype "input"))
      (node (ref "S1") (pin "1") (pinfunction "SDA_1") (pintype "unspecified"))
      (node (ref "U7") (pin "13") (pinfunction "SDA_13") (pintype "input"))
      (node (ref "U8") (pin "33") (pinfunction "IO21_33") (pintype "input"))
    )
    (net (code "13") (name "/IO0") (class "Default")
      (node (ref "Q4") (pin "3") (pinfunction "C_3") (pintype "input"))
      (node (ref "U8") (pin "25") (pinfunction "IO0_25") (pintype "input"))
    )
    (net (code "14") (name "/KEY1") (class "Default")
      (node (ref "C22") (pin "1") (pinfunction "1_1") (pintype "input"))
      (node (ref "KEY1") (pin "2") (pinfunction "2_2") (pintype "input"))
      (node (ref "R22") (pin "2") (pinfunction "2_2") (pintype "input"))
      (node (ref "U8") (pin "9") (pinfunction "IO33_9") (pintype "input"))
    )
    (net (code "15") (name "/KEY2") (class "Default")
      (node (ref "C23") (pin "1") (pinfunction "1_1") (pintype "input"))
      (node (ref "KEY2") (pin "2") (pinfunction "2_2") (pintype "input"))
      (node (ref "R23") (pin "2") (pinfunction "2_2") (pintype "input"))
      (node (ref "U8") (pin "11") (pinfunction "IO26_11") (pintype "input"))
    )
    (net (code "16") (name "/KEY3") (class "Default")
      (node (ref "C24") (pin "1") (pinfunction "1_1") (pintype "input"))
      (node (ref "KEY3") (pin "2") (pinfunction "2_2") (pintype "input"))
      (node (ref "R24") (pin "2") (pinfunction "2_2") (pintype "input"))
      (node (ref "U8") (pin "12") (pinfunction "IO27_12") (pintype "input"))
    )
    (net (code "17") (name "/MISO") (class "Default")
      (node (ref "CARD1") (pin "7") (pinfunction "DAT0_7") (pintype "input"))
      (node (ref "R18") (pin "2") (pinfunction "2_2") (pintype "input"))
      (node (ref "U8") (pin "31") (pinfunction "IO19_31") (pintype "input"))
    )
    (net (code "18") (name "/PREVGH") (class "Default")
      (node (ref "C12") (pin "1") (pinfunction "1_1") (pintype "input"))
      (node (ref "C20") (pin "1") (pinfunction "1_1") (pintype "input"))
      (node (ref "D8") (pin "1") (pinfunction "K_1") (pintype "input"))
      (node (ref "FPC2") (pin "21") (pinfunction "21_21") (pintype "input"))
    )
    (net (code "19") (name "/PREVGL") (class "Default")
      (node (ref "C14") (pin "1") (pinfunction "1_1") (pintype "input"))
      (node (ref "D7") (pin "2") (pinfunction "A_2") (pintype "input"))
      (node (ref "FPC2") (pin "23") (pinfunction "23_23") (pintype "input"))
    )
    (net (code "20") (name "/RESE") (class "Default")
      (node (ref "FPC2") (pin "3") (pinfunction "3_3") (pintype "input"))
      (node (ref "Q3") (pin "2") (pinfunction "S_2") (pintype "input"))
      (node (ref "R14") (pin "2") (pinfunction "2_2") (pintype "input"))
    )
    (net (code "21") (name "/REST") (class "Default")
      (node (ref "FPC2") (pin "10") (pinfunction "10_10") (pintype "input"))
      (node (ref "U8") (pin "27") (pinfunction "IO16_27") (pintype "input"))
    )
    (net (code "22") (name "/RTS") (class "Default")
      (node (ref "Q5") (pin "3") (pinfunction "C_3") (pintype "input"))
      (node (ref "R8") (pin "1") (pinfunction "1_1") (pintype "input"))
      (node (ref "RESET1") (pin "1") (pinfunction "1_1") (pintype "input"))
      (node (ref "U8") (pin "3") (pinfunction "EN_3") (pintype "input"))
    )
    (net (code "23") (name "/RXD0") (class "Default")
      (node (ref "R11") (pin "1") (pinfunction "1_1") (pintype "input"))
      (node (ref "U4") (pin "2") (pinfunction "TXD_2") (pintype "input"))
      (node (ref "U8") (pin "34") (pinfunction "U0RXD_34") (pintype "input"))
    )
    (net (code "24") (name "/SCLK") (class "Default")
      (node (ref "CARD1") (pin "5") (pinfunction "CLX_5") (pintype "input"))
      (node (ref "FPC2") (pin "13") (pinfunction "13_13") (pintype "input"))
      (node (ref "R19") (pin "2") (pinfunction "2_2") (pintype "input"))
      (node (ref "U8") (pin "30") (pinfunction "IO18_30") (pintype "input"))
    )
    (net (code "25") (name "/SD_SS") (class "Default")
      (node (ref "CARD1") (pin "2") (pinfunction "CD/DAT3_2") (pintype "input"))
      (node (ref "R21") (pin "2") (pinfunction "2_2") (pintype "input"))
      (node (ref "U8") (pin "23") (pinfunction "IO15_23") (pintype "input"))
    )
    (net (code "26") (name "/TXD0") (class "Default")
      (node (ref "R10") (pin "1") (pinfunction "1_1") (pintype "input"))
      (node (ref "U4") (pin "3") (pinfunction "RXD_3") (pintype "input"))
      (node (ref "U8") (pin "35") (pinfunction "U0TXD_35") (pintype "input"))
    )
    (net (code "27") (name "3V3") (class "Default")
      (node (ref "C16") (pin "1") (pinfunction "1_1") (pintype "input"))
      (node (ref "C17") (pin "1") (pinfunction "1_1") (pintype "input"))
      (node (ref "C19") (pin "1") (pinfunction "1_1") (pintype "input"))
      (node (ref "C21") (pin "1") (pinfunction "1_1") (pintype "input"))
      (node (ref "C3") (pin "2") (pinfunction "2_2") (pintype "input"))
      (node (ref "C4") (pin "2") (pinfunction "2_2") (pintype "input"))
      (node (ref "CARD1") (pin "4") (pinfunction "VDD_4") (pintype "input"))
      (node (ref "FPC2") (pin "15") (pinfunction "15_15") (pintype "input"))
      (node (ref "FPC2") (pin "16") (pinfunction "16_16") (pintype "input"))
      (node (ref "L1") (pin "1") (pinfunction "1_1") (pintype "input"))
      (node (ref "R10") (pin "2") (pinfunction "2_2") (pintype "input"))
      (node (ref "R11") (pin "2") (pinfunction "2_2") (pintype "input"))
      (node (ref "R12") (pin "2") (pinfunction "2_2") (pintype "input"))
      (node (ref "R18") (pin "1") (pinfunction "1_1") (pintype "input"))
      (node (ref "R19") (pin "1") (pinfunction "1_1") (pintype "input"))
      (node (ref "R20") (pin "1") (pinfunction "1_1") (pintype "input"))
      (node (ref "R21") (pin "1") (pinfunction "1_1") (pintype "input"))
      (node (ref "R22") (pin "1") (pinfunction "1_1") (pintype "input"))
      (node (ref "R23") (pin "1") (pinfunction "1_1") (pintype "input"))
      (node (ref "R24") (pin "1") (pinfunction "1_1") (pintype "input"))
      (node (ref "R8") (pin "2") (pinfunction "2_2") (pintype "input"))
      (node (ref "R9") (pin "2") (pinfunction "2_2") (pintype "input"))
      (node (ref "S1") (pin "5") (pinfunction "VDD_5") (pintype "unspecified"))
      (node (ref "U2") (pin "5") (pinfunction "VOUT_5") (pintype "input"))
      (node (ref "U4") (pin "16") (pinfunction "VCC_16") (pintype "input"))
      (node (ref "U4") (pin "4") (pinfunction "V3_4") (pintype "input"))
      (node (ref "U8") (pin "2") (pinfunction "3V3_2") (pintype "input"))
    )
    (net (code "28") (name "GND") (class "Default")
      (node (ref "C1") (pin "1") (pinfunction "1_1") (pintype "input"))
      (node (ref "C10") (pin "2") (pinfunction "2_2") (pintype "input"))
      (node (ref "C11") (pin "2") (pinfunction "2_2") (pintype "input"))
      (node (ref "C12") (pin "2") (pinfunction "2_2") (pintype "input"))
      (node (ref "C13") (pin "2") (pinfunction "2_2") (pintype "input"))
      (node (ref "C14") (pin "2") (pinfunction "2_2") (pintype "input"))
      (node (ref "C15") (pin "2") (pinfunction "2_2") (pintype "input"))
      (node (ref "C16") (pin "2") (pinfunction "2_2") (pintype "input"))
      (node (ref "C17") (pin "2") (pinfunction "2_2") (pintype "input"))
      (node (ref "C19") (pin "2") (pinfunction "2_2") (pintype "input"))
      (node (ref "C2") (pin "1") (pinfunction "1_1") (pintype "input"))
      (node (ref "C20") (pin "2") (pinfunction "2_2") (pintype "input"))
      (node (ref "C21") (pin "2") (pinfunction "2_2") (pintype "input"))
      (node (ref "C22") (pin "2") (pinfunction "2_2") (pintype "input"))
      (node (ref "C23") (pin "2") (pinfunction "2_2") (pintype "input"))
      (node (ref "C24") (pin "2") (pinfunction "2_2") (pintype "input"))
      (node (ref "C3") (pin "1") (pinfunction "1_1") (pintype "input"))
      (node (ref "C4") (pin "1") (pinfunction "1_1") (pintype "input"))
      (node (ref "C5") (pin "1") (pinfunction "1_1") (pintype "input"))
      (node (ref "C6") (pin "1") (pinfunction "1_1") (pintype "input"))
      (node (ref "C7") (pin "2") (pinfunction "2_2") (pintype "input"))
      (node (ref "C8") (pin "2") (pinfunction "2_2") (pintype "input"))
      (node (ref "C9") (pin "2") (pinfunction "2_2") (pintype "input"))
      (node (ref "CARD1") (pin "10") (pinfunction "SHELL_10") (pintype "input"))
      (node (ref "CARD1") (pin "11") (pinfunction "SHELL_11") (pintype "input"))
      (node (ref "CARD1") (pin "12") (pinfunction "SHELL_12") (pintype "input"))
      (node (ref "CARD1") (pin "13") (pinfunction "SHELL_13") (pintype "input"))
      (node (ref "CARD1") (pin "6") (pinfunction "VSS_6") (pintype "input"))
      (node (ref "D1") (pin "1") (pinfunction "1_1") (pintype "input"))
      (node (ref "D6") (pin "1") (pinfunction "K_1") (pintype "input"))
      (node (ref "FPC2") (pin "17") (pinfunction "17_17") (pintype "input"))
      (node (ref "FPC2") (pin "25") (pinfunction "25_25") (pintype "input"))
      (node (ref "FPC2") (pin "26") (pinfunction "26_26") (pintype "input"))
      (node (ref "FPC2") (pin "8") (pinfunction "8_8") (pintype "input"))
      (node (ref "KEY1") (pin "1") (pinfunction "1_1") (pintype "input"))
      (node (ref "KEY1") (pin "3") (pinfunction "3_3") (pintype "input"))
      (node (ref "KEY1") (pin "4") (pinfunction "4_4") (pintype "input"))
      (node (ref "KEY2") (pin "1") (pinfunction "1_1") (pintype "input"))
      (node (ref "KEY2") (pin "3") (pinfunction "3_3") (pintype "input"))
      (node (ref "KEY2") (pin "4") (pinfunction "4_4") (pintype "input"))
      (node (ref "KEY3") (pin "1") (pinfunction "1_1") (pintype "input"))
      (node (ref "KEY3") (pin "3") (pinfunction "3_3") (pintype "input"))
      (node (ref "KEY3") (pin "4") (pinfunction "4_4") (pintype "input"))
      (node (ref "Q2") (pin "2") (pinfunction "S_2") (pintype "input"))
      (node (ref "Q7") (pin "2") (pinfunction "E_2") (pintype "input"))
      (node (ref "R1") (pin "1") (pinfunction "1_1") (pintype "input"))
      (node (ref "R13") (pin "1") (pinfunction "1_1") (pintype "input"))
      (node (ref "R14") (pin "1") (pinfunction "1_1") (pintype "input"))
      (node (ref "R16") (pin "1") (pinfunction "1_1") (pintype "input"))
      (node (ref "R2") (pin "1") (pinfunction "1_1") (pintype "input"))
      (node (ref "R3") (pin "1") (pinfunction "1_1") (pintype "input"))
      (node (ref "R5") (pin "1") (pinfunction "1_1") (pintype "input"))
      (node (ref "RESET1") (pin "2") (pinfunction "2_2") (pintype "input"))
      (node (ref "RESET1") (pin "3") (pinfunction "3_3") (pintype "input"))
      (node (ref "RESET1") (pin "4") (pinfunction "4_4") (pintype "input"))
      (node (ref "S1") (pin "2") (pinfunction "ADDR_2") (pintype "unspecified"))
      (node (ref "S1") (pin "7") (pinfunction "R_7") (pintype "unspecified"))
      (node (ref "S1") (pin "8") (pinfunction "VSS_8") (pintype "unspecified"))
      (node (ref "S1") (pin "9") (pinfunction "EPAD_9") (pintype "unspecified"))
      (node (ref "U1") (pin "1") (pinfunction "TEMP_1") (pintype "input"))
      (node (ref "U1") (pin "3") (pinfunction "GND_3") (pintype "input"))
      (node (ref "U1") (pin "9") (pinfunction "EP_9") (pintype "input"))
      (node (ref "U17") (pin "1") (pinfunction "1_1") (pintype "unspecified"))
      (node (ref "U17") (pin "2") (pinfunction "2_2") (pintype "unspecified"))
      (node (ref "U2") (pin "2") (pinfunction "VSS_2") (pintype "input"))
      (node (ref "U7") (pin "11") (pinfunction "GND_11") (pintype "input"))
      (node (ref "U7") (pin "7") (pinfunction "FOE_7") (pintype "input"))
      (node (ref "U8") (pin "1") (pinfunction "GND_1") (pintype "input"))
      (node (ref "U8") (pin "15") (pinfunction "GND_15") (pintype "input"))
      (node (ref "U8") (pin "38") (pinfunction "GND_38") (pintype "input"))
      (node (ref "U8") (pin "39") (pinfunction "EP_39") (pintype "input"))
      (node (ref "USB1") (pin "1") (pinfunction "SHELL_1") (pintype "input"))
      (node (ref "USB1") (pin "2") (pinfunction "SHELL_2") (pintype "input"))
      (node (ref "USB1") (pin "3") (pinfunction "SHELL_3") (pintype "input"))
      (node (ref "USB1") (pin "4") (pinfunction "SHELL_4") (pintype "input"))
      (node (ref "USB1") (pin "A1B12") (pinfunction "GND_A1B12") (pintype "input"))
      (node (ref "USB1") (pin "B1A12") (pinfunction "GND_B1A12") (pintype "input"))
    )
    (net (code "29") (name "Net-(BUZZER1-Pad1)") (class "Default")
      (node (ref "BUZZER1") (pin "1") (pinfunction "1_1") (pintype "input"))
      (node (ref "R17") (pin "2") (pinfunction "2_2") (pintype "input"))
    )
    (net (code "30") (name "Net-(C7-Pad1)") (class "Default")
      (node (ref "C7") (pin "1") (pinfunction "1_1") (pintype "input"))
      (node (ref "FPC2") (pin "4") (pinfunction "4_4") (pintype "input"))
    )
    (net (code "31") (name "Net-(C8-Pad1)") (class "Default")
      (node (ref "C8") (pin "1") (pinfunction "1_1") (pintype "input"))
      (node (ref "FPC2") (pin "5") (pinfunction "5_5") (pintype "input"))
    )
    (net (code "32") (name "Net-(C9-Pad1)") (class "Default")
      (node (ref "C9") (pin "1") (pinfunction "1_1") (pintype "input"))
      (node (ref "FPC2") (pin "18") (pinfunction "18_18") (pintype "input"))
    )
    (net (code "33") (name "Net-(C10-Pad1)") (class "Default")
      (node (ref "C10") (pin "1") (pinfunction "1_1") (pintype "input"))
      (node (ref "FPC2") (pin "19") (pinfunction "19_19") (pintype "input"))
    )
    (net (code "34") (name "Net-(C11-Pad1)") (class "Default")
      (node (ref "C11") (pin "1") (pinfunction "1_1") (pintype "input"))
      (node (ref "FPC2") (pin "20") (pinfunction "20_20") (pintype "input"))
    )
    (net (code "35") (name "Net-(C13-Pad1)") (class "Default")
      (node (ref "C13") (pin "1") (pinfunction "1_1") (pintype "input"))
      (node (ref "FPC2") (pin "22") (pinfunction "22_22") (pintype "input"))
    )
    (net (code "36") (name "Net-(C15-Pad1)") (class "Default")
      (node (ref "C15") (pin "1") (pinfunction "1_1") (pintype "input"))
      (node (ref "FPC2") (pin "24") (pinfunction "24_24") (pintype "input"))
    )
    (net (code "37") (name "Net-(CHRG1-A)") (class "Default")
      (node (ref "CHRG1") (pin "1") (pinfunction "A_1") (pintype "input"))
      (node (ref "DONE1") (pin "1") (pinfunction "A_1") (pintype "input"))
      (node (ref "R4") (pin "1") (pinfunction "1_1") (pintype "input"))
    )
    (net (code "38") (name "Net-(CHRG1-C)") (class "Default")
      (node (ref "CHRG1") (pin "2") (pinfunction "C_2") (pintype "input"))
      (node (ref "U1") (pin "7") (pinfunction "CHRG_7") (pintype "input"))
    )
    (net (code "39") (name "Net-(D4-C)") (class "Default")
      (node (ref "C2") (pin "2") (pinfunction "2_2") (pintype "input"))
      (node (ref "D4") (pin "1") (pinfunction "C_1") (pintype "input"))
      (node (ref "Q1") (pin "2") (pinfunction "S_2") (pintype "input"))
      (node (ref "U2") (pin "1") (pinfunction "VIN_1") (pintype "input"))
      (node (ref "U2") (pin "3") (pinfunction "CE_3") (pintype "input"))
    )
    (net (code "40") (name "Net-(D5-K)") (class "Default")
      (node (ref "C5") (pin "2") (pinfunction "2_2") (pintype "input"))
      (node (ref "C6") (pin "2") (pinfunction "2_2") (pintype "input"))
      (node (ref "D5") (pin "1") (pinfunction "K_1") (pintype "input"))
      (node (ref "U7") (pin "6") (pinfunction "VDD_6") (pintype "input"))
    )
    (net (code "41") (name "Net-(D6-A)") (class "Default")
      (node (ref "C18") (pin "1") (pinfunction "1_1") (pintype "input"))
      (node (ref "D6") (pin "2") (pinfunction "A_2") (pintype "input"))
      (node (ref "D7") (pin "1") (pinfunction "K_1") (pintype "input"))
    )
    (net (code "42") (name "Net-(D8-A)") (class "Default")
      (node (ref "C18") (pin "2") (pinfunction "2_2") (pintype "input"))
      (node (ref "D8") (pin "2") (pinfunction "A_2") (pintype "input"))
      (node (ref "L1") (pin "2") (pinfunction "2_2") (pintype "input"))
      (node (ref "Q3") (pin "3") (pinfunction "D_3") (pintype "input"))
    )
    (net (code "43") (name "Net-(DONE1-C)") (class "Default")
      (node (ref "DONE1") (pin "2") (pinfunction "C_2") (pintype "input"))
      (node (ref "U1") (pin "6") (pinfunction "STDBY_6") (pintype "input"))
    )
    (net (code "44") (name "Net-(Q2-D)") (class "Default")
      (node (ref "Q2") (pin "3") (pinfunction "D_3") (pintype "input"))
      (node (ref "U4") (pin "1") (pinfunction "GND_1") (pintype "input"))
    )
    (net (code "45") (name "Net-(Q4-B)") (class "Default")
      (node (ref "Q4") (pin "1") (pinfunction "B_1") (pintype "input"))
      (node (ref "R7") (pin "1") (pinfunction "1_1") (pintype "input"))
    )
    (net (code "46") (name "Net-(Q4-E)") (class "Default")
      (node (ref "Q4") (pin "2") (pinfunction "E_2") (pintype "input"))
      (node (ref "R6") (pin "2") (pinfunction "2_2") (pintype "input"))
      (node (ref "U4") (pin "13") (pinfunction "DTR#_13") (pintype "input"))
    )
    (net (code "47") (name "Net-(Q5-B)") (class "Default")
      (node (ref "Q5") (pin "1") (pinfunction "B_1") (pintype "input"))
      (node (ref "R6") (pin "1") (pinfunction "1_1") (pintype "input"))
    )
    (net (code "48") (name "Net-(Q5-E)") (class "Default")
      (node (ref "Q5") (pin "2") (pinfunction "E_2") (pintype "input"))
      (node (ref "R7") (pin "2") (pinfunction "2_2") (pintype "input"))
      (node (ref "U4") (pin "14") (pinfunction "RTS#_14") (pintype "input"))
    )
    (net (code "49") (name "Net-(Q7-B)") (class "Default")
      (node (ref "Q7") (pin "1") (pinfunction "B_1") (pintype "input"))
      (node (ref "R15") (pin "1") (pinfunction "1_1") (pintype "input"))
      (node (ref "R16") (pin "2") (pinfunction "2_2") (pintype "input"))
    )
    (net (code "50") (name "Net-(Q7-C)") (class "Default")
      (node (ref "BUZZER1") (pin "2") (pinfunction "2_2") (pintype "input"))
      (node (ref "Q7") (pin "3") (pinfunction "C_3") (pintype "input"))
    )
    (net (code "51") (name "Net-(U1-PROG)") (class "Default")
      (node (ref "R3") (pin "2") (pinfunction "2_2") (pintype "input"))
      (node (ref "U1") (pin "2") (pinfunction "PROG_2") (pintype "input"))
    )
    (net (code "52") (name "Net-(USB1-CC1)") (class "Default")
      (node (ref "R1") (pin "2") (pinfunction "2_2") (pintype "input"))
      (node (ref "USB1") (pin "A5") (pinfunction "CC1_A5") (pintype "input"))
      (node (ref "USB1") (pin "B5") (pinfunction "CC2_B5") (pintype "input"))
    )
    (net (code "53") (name "unconnected-(CARD1-CD-Pad9)") (class "Default")
      (node (ref "CARD1") (pin "9") (pinfunction "CD_9") (pintype "input+no_connect"))
    )
    (net (code "54") (name "unconnected-(CARD1-DAT1-Pad8)") (class "Default")
      (node (ref "CARD1") (pin "8") (pinfunction "DAT1_8") (pintype "input+no_connect"))
    )
    (net (code "55") (name "unconnected-(CARD1-DAT2-Pad1)") (class "Default")
      (node (ref "CARD1") (pin "1") (pinfunction "DAT2_1") (pintype "input+no_connect"))
    )
    (net (code "56") (name "unconnected-(FPC2-Pad1)") (class "Default")
      (node (ref "FPC2") (pin "1") (pinfunction "1_1") (pintype "input+no_connect"))
    )
    (net (code "57") (name "unconnected-(FPC2-Pad6)") (class "Default")
      (node (ref "FPC2") (pin "6") (pinfunction "6_6") (pintype "input+no_connect"))
    )
    (net (code "58") (name "unconnected-(FPC2-Pad7)") (class "Default")
      (node (ref "FPC2") (pin "7") (pinfunction "7_7") (pintype "input+no_connect"))
    )
    (net (code "59") (name "unconnected-(S1-ALERT-Pad3)") (class "Default")
      (node (ref "S1") (pin "3") (pinfunction "ALERT_3") (pintype "unspecified+no_connect"))
    )
    (net (code "60") (name "unconnected-(S1-NRESET-Pad6)") (class "Default")
      (node (ref "S1") (pin "6") (pinfunction "NRESET_6") (pintype "unspecified+no_connect"))
    )
    (net (code "61") (name "unconnected-(U2-NC-Pad4)") (class "Default")
      (node (ref "U2") (pin "4") (pinfunction "NC_4") (pintype "input+no_connect"))
    )
    (net (code "62") (name "unconnected-(U4-CTS#-Pad9)") (class "Default")
      (node (ref "U4") (pin "9") (pinfunction "CTS#_9") (pintype "input+no_connect"))
    )
    (net (code "63") (name "unconnected-(U4-DCD#-Pad12)") (class "Default")
      (node (ref "U4") (pin "12") (pinfunction "DCD#_12") (pintype "input+no_connect"))
    )
    (net (code "64") (name "unconnected-(U4-DSR#-Pad10)") (class "Default")
      (node (ref "U4") (pin "10") (pinfunction "DSR#_10") (pintype "input+no_connect"))
    )
    (net (code "65") (name "unconnected-(U4-NC.-Pad7)") (class "Default")
      (node (ref "U4") (pin "7") (pinfunction "NC._7") (pintype "input+no_connect"))
    )
    (net (code "66") (name "unconnected-(U4-NC.-Pad8)") (class "Default")
      (node (ref "U4") (pin "8") (pinfunction "NC._8") (pintype "input+no_connect"))
    )
    (net (code "67") (name "unconnected-(U4-R232-Pad15)") (class "Default")
      (node (ref "U4") (pin "15") (pinfunction "R232_15") (pintype "input+no_connect"))
    )
    (net (code "68") (name "unconnected-(U4-RI#-Pad11)") (class "Default")
      (node (ref "U4") (pin "11") (pinfunction "RI#_11") (pintype "input+no_connect"))
    )
    (net (code "69") (name "unconnected-(U7-FOUT-Pad3)") (class "Default")
      (node (ref "U7") (pin "3") (pinfunction "FOUT_3") (pintype "input+no_connect"))
    )
    (net (code "70") (name "unconnected-(U7-INT#-Pad10)") (class "Default")
      (node (ref "U7") (pin "10") (pinfunction "INT#_10") (pintype "input+no_connect"))
    )
    (net (code "71") (name "unconnected-(U7-NC-Pad4)") (class "Default")
      (node (ref "U7") (pin "4") (pinfunction "NC_4") (pintype "input+no_connect"))
    )
    (net (code "72") (name "unconnected-(U7-NC-Pad8)") (class "Default")
      (node (ref "U7") (pin "8") (pinfunction "NC_8") (pintype "input+no_connect"))
    )
    (net (code "73") (name "unconnected-(U7-NC-Pad9)") (class "Default")
      (node (ref "U7") (pin "9") (pinfunction "NC_9") (pintype "input+no_connect"))
    )
    (net (code "74") (name "unconnected-(U7-NC-Pad14)") (class "Default")
      (node (ref "U7") (pin "14") (pinfunction "NC_14") (pintype "input+no_connect"))
    )
    (net (code "75") (name "unconnected-(U7-T1-Pad1)") (class "Default")
      (node (ref "U7") (pin "1") (pinfunction "T1_1") (pintype "input+no_connect"))
    )
    (net (code "76") (name "unconnected-(U7-T2-Pad12)") (class "Default")
      (node (ref "U7") (pin "12") (pinfunction "T2_12") (pintype "input+no_connect"))
    )
    (net (code "77") (name "unconnected-(U7-TEST-Pad5)") (class "Default")
      (node (ref "U7") (pin "5") (pinfunction "TEST_5") (pintype "input+no_connect"))
    )
    (net (code "78") (name "unconnected-(U8-CLK-Pad20)") (class "Default")
      (node (ref "U8") (pin "20") (pinfunction "CLK_20") (pintype "input+no_connect"))
    )
    (net (code "79") (name "unconnected-(U8-CMD-Pad19)") (class "Default")
      (node (ref "U8") (pin "19") (pinfunction "CMD_19") (pintype "input+no_connect"))
    )
    (net (code "80") (name "unconnected-(U8-IO2-Pad24)") (class "Default")
      (node (ref "U8") (pin "24") (pinfunction "IO2_24") (pintype "input+no_connect"))
    )
    (net (code "81") (name "unconnected-(U8-IO12-Pad14)") (class "Default")
      (node (ref "U8") (pin "14") (pinfunction "IO12_14") (pintype "input+no_connect"))
    )
    (net (code "82") (name "unconnected-(U8-IO13-Pad16)") (class "Default")
      (node (ref "U8") (pin "16") (pinfunction "IO13_16") (pintype "input+no_connect"))
    )
    (net (code "83") (name "unconnected-(U8-IO14-Pad13)") (class "Default")
      (node (ref "U8") (pin "13") (pinfunction "IO14_13") (pintype "input+no_connect"))
    )
    (net (code "84") (name "unconnected-(U8-IO32-Pad8)") (class "Default")
      (node (ref "U8") (pin "8") (pinfunction "IO32_8") (pintype "input+no_connect"))
    )
    (net (code "85") (name "unconnected-(U8-IO34-Pad6)") (class "Default")
      (node (ref "U8") (pin "6") (pinfunction "IO34_6") (pintype "input+no_connect"))
    )
    (net (code "86") (name "unconnected-(U8-IO35-Pad7)") (class "Default")
      (node (ref "U8") (pin "7") (pinfunction "IO35_7") (pintype "input+no_connect"))
    )
    (net (code "87") (name "unconnected-(U8-NC-Pad32)") (class "Default")
      (node (ref "U8") (pin "32") (pinfunction "NC_32") (pintype "input+no_connect"))
    )
    (net (code "88") (name "unconnected-(U8-SD2-Pad17)") (class "Default")
      (node (ref "U8") (pin "17") (pinfunction "SD2_17") (pintype "input+no_connect"))
    )
    (net (code "89") (name "unconnected-(U8-SD3-Pad18)") (class "Default")
      (node (ref "U8") (pin "18") (pinfunction "SD3_18") (pintype "input+no_connect"))
    )
    (net (code "90") (name "unconnected-(U8-SDI-Pad22)") (class "Default")
      (node (ref "U8") (pin "22") (pinfunction "SDI_22") (pintype "input+no_connect"))
    )
    (net (code "91") (name "unconnected-(U8-SDO-Pad21)") (class "Default")
      (node (ref "U8") (pin "21") (pinfunction "SDO_21") (pintype "input+no_connect"))
    )
    (net (code "92") (name "unconnected-(U8-SENSOR_VN-Pad5)") (class "Default")
      (node (ref "U8") (pin "5") (pinfunction "SENSOR_VN_5") (pintype "input+no_connect"))
    )
    (net (code "93") (name "unconnected-(U8-SENSOR_VP-Pad4)") (class "Default")
      (node (ref "U8") (pin "4") (pinfunction "SENSOR_VP_4") (pintype "input+no_connect"))
    )
    (net (code "94") (name "unconnected-(USB1-SBU1-PadA8)") (class "Default")
      (node (ref "USB1") (pin "A8") (pinfunction "SBU1_A8") (pintype "input+no_connect"))
    )
    (net (code "95") (name "unconnected-(USB1-SBU2-PadB8)") (class "Default")
      (node (ref "USB1") (pin "B8") (pinfunction "SBU2_B8") (pintype "input+no_connect"))
    )
  )
)
